# DM3390_Power_Supply.net
KiCad netlist of a schematic drawn in Altium Designer
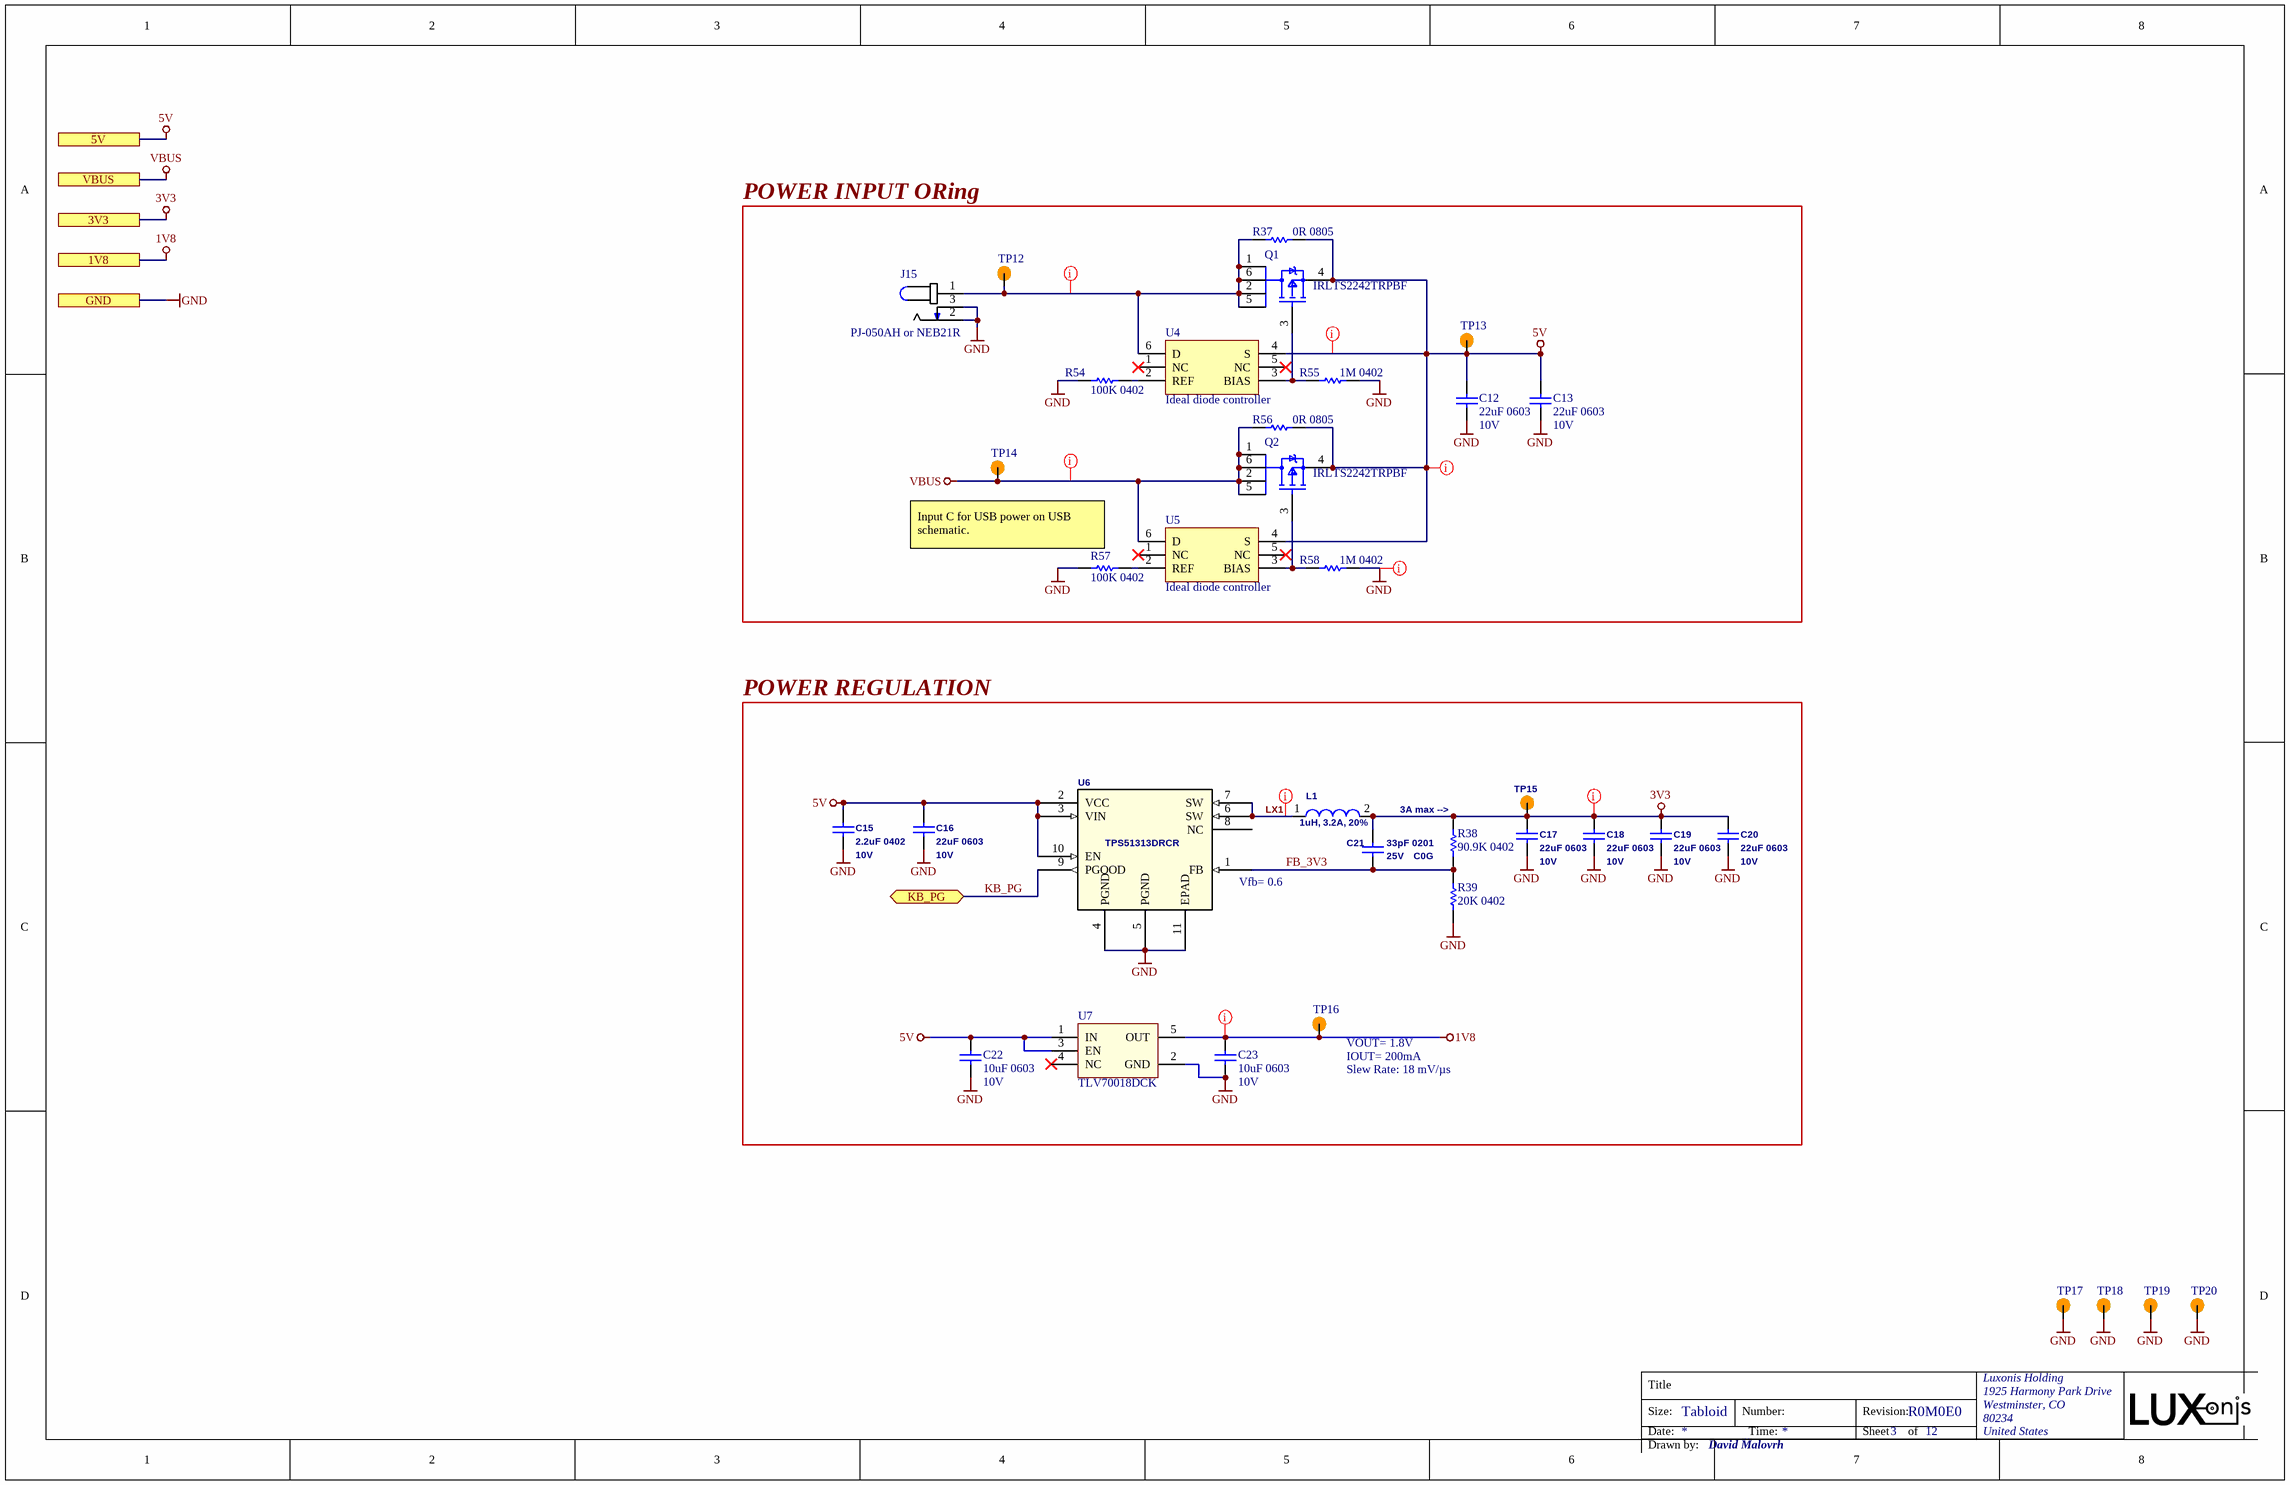
[diagram p0: DM3390_Power_Supply.SchDoc]

(export (version "E")
  (design (tool "Eeschema 10.0.6"))
  (components
    (comp (ref "C12")
      (value "22uF 0603")
      (footprint "CAP_Altium_Vault_Generic:CAPC0603(1608)100_L")
      (description "CAP CER 22UF 10V X5R 0603 20%")
      (fields (field (name "TOLERANCE") "20%") (field (name "VOLTAGE RATING") "10V"))
      (libsource (lib "LuxonisMaster") (part "GRM188R61A226ME15D"))
    )
    (comp (ref "C13")
      (value "22uF 0603")
      (footprint "CAP_Altium_Vault_Generic:CAPC0603(1608)100_L")
      (description "CAP CER 22UF 10V X5R 0603 20%")
      (fields (field (name "TOLERANCE") "20%") (field (name "VOLTAGE RATING") "10V"))
      (libsource (lib "LuxonisMaster") (part "GRM188R61A226ME15D"))
    )
    (comp (ref "C15")
      (value "2.2uF 0402")
      (footprint "CAP_Altium_Vault_Generic:CAPC0402(1005)70_L")
      (description "CAP CER 2.2UF 10V X5R 0402 10%")
      (fields (field (name "TOLERANCE") "10%") (field (name "VOLTAGE RATING") "10V"))
      (libsource (lib "LuxonisMaster") (part "GRM155R61A225KE95D"))
    )
    (comp (ref "C16")
      (value "22uF 0603")
      (footprint "CAP_Altium_Vault_Generic:CAPC0603(1608)100_L")
      (description "CAP CER 22UF 10V X5R 0603 20%")
      (fields (field (name "TOLERANCE") "20%") (field (name "VOLTAGE RATING") "10V"))
      (libsource (lib "LuxonisMaster") (part "GRM188R61A226ME15D"))
    )
    (comp (ref "C17")
      (value "22uF 0603")
      (footprint "CAP_Altium_Vault_Generic:CAPC0603(1608)100_L")
      (description "CAP CER 22UF 10V X5R 0603 20%")
      (fields (field (name "TOLERANCE") "20%") (field (name "VOLTAGE RATING") "10V"))
      (libsource (lib "LuxonisMaster") (part "GRM188R61A226ME15D"))
    )
    (comp (ref "C18")
      (value "22uF 0603")
      (footprint "CAP_Altium_Vault_Generic:CAPC0603(1608)100_L")
      (description "CAP CER 22UF 10V X5R 0603 20%")
      (fields (field (name "TOLERANCE") "20%") (field (name "VOLTAGE RATING") "10V"))
      (libsource (lib "LuxonisMaster") (part "GRM188R61A226ME15D"))
    )
    (comp (ref "C19")
      (value "22uF 0603")
      (footprint "CAP_Altium_Vault_Generic:CAPC0603(1608)100_L")
      (description "CAP CER 22UF 10V X5R 0603 20%")
      (fields (field (name "TOLERANCE") "20%") (field (name "VOLTAGE RATING") "10V"))
      (libsource (lib "LuxonisMaster") (part "GRM188R61A226ME15D"))
    )
    (comp (ref "C20")
      (value "22uF 0603")
      (footprint "CAP_Altium_Vault_Generic:CAPC0603(1608)100_L")
      (description "CAP CER 22UF 10V X5R 0603 20%")
      (fields (field (name "TOLERANCE") "20%") (field (name "VOLTAGE RATING") "10V"))
      (libsource (lib "LuxonisMaster") (part "GRM188R61A226ME15D"))
    )
    (comp (ref "C21")
      (value "33pF 0201")
      (footprint "CAP_Altium_Vault_Generic:CAPC0201(0603)33_L")
      (description "CAP CER 33PF 25V C0G/NP0 0201")
      (fields
        (field (name "TOLERANCE") "5%")
        (field (name "VOLTAGE RATING") "25V")
        (field (name "DIELECTRIC") "C0G")
      )
      (libsource (lib "LuxonisMaster") (part "GRM0335C1E330JA01D"))
    )
    (comp (ref "C22")
      (value "10uF 0603")
      (footprint "CAP_Altium_Vault_Generic:CAPC0603(1608)100_L")
      (description "CAP CER 10UF 10V X5R 0603 20%")
      (fields (field (name "TOLERANCE") "20%") (field (name "VOLTAGE RATING") "10V"))
      (libsource (lib "LuxonisMaster") (part "GRM188R61A106ME69D"))
    )
    (comp (ref "C23")
      (value "10uF 0603")
      (footprint "CAP_Altium_Vault_Generic:CAPC0603(1608)100_L")
      (description "CAP CER 10UF 10V X5R 0603 20%")
      (fields (field (name "TOLERANCE") "20%") (field (name "VOLTAGE RATING") "10V"))
      (libsource (lib "LuxonisMaster") (part "GRM188R61A106ME69D"))
    )
    (comp (ref "J15")
      (value "PJ-050AH or NEB21R")
      (footprint "LuxonisMaster:PJ-050AH/NEB21R_COMBO")
      (description "CONN POWER PIN 2 POS RA PTH Barrel jack 2.1mm x 5.5mm combo footprint")
      (libsource (lib "LuxonisMaster") (part "PJ-050AH/NEB21R_COMBO"))
    )
    (comp (ref "L1")
      (value "1uH, 3.2A, 20%")
      (footprint "LuxonisMaster:DFE252012P-1R0M=P2")
      (description "FIXED IND 1UH 3.2A 42 MOHM SMD")
      (fields
        (field (name "MANUFACTURER") "Murata")
        (field (name "MANUFACTURER PART NUMBER") "DFE252012P-1R0M=P2")
      )
      (libsource (lib "LuxonisMaster") (part "DFE252012P-1R0M=P2"))
    )
    (comp (ref "Q1")
      (value "IRLTS2242TRPBF")
      (footprint "TSOP-6-MFG")
      (description "MOSFET P-CH 20V 6.9A 6TSOP")
      (libsource (lib "LuxonisMaster") (part "IRLTS2242TRPBF"))
    )
    (comp (ref "Q2")
      (value "IRLTS2242TRPBF")
      (footprint "TSOP-6-MFG")
      (description "MOSFET P-CH 20V 6.9A 6TSOP")
      (libsource (lib "LuxonisMaster") (part "IRLTS2242TRPBF"))
    )
    (comp (ref "R37")
      (value "0R 0805")
      (footprint "RESC0805(2012)_L")
      (description "RES SMD 0.0R OHM 1% 1/8W 0805")
      (libsource (lib "LuxonisMaster") (part "CRCW08050000Z0EA"))
    )
    (comp (ref "R38")
      (value "90.9K 0402")
      (footprint "RES_Altium_Vault_Generic:RESC0402(1005)_L")
      (description "RES SMD 90.9K OHM 1% 1/16W 0402")
      (fields (field (name "TOLERANCE") "1%"))
      (libsource (lib "LuxonisMaster") (part "CRCW040290K9FKED"))
    )
    (comp (ref "R39")
      (value "20K 0402")
      (footprint "RES_Altium_Vault_Generic:RESC0402(1005)_L")
      (fields
        (field (name "MANUFACTURER") "Yageo")
        (field (name "MANUFACTURER PART NUMBER") "RC0402FR-0720KL")
        (field (name "TOLERANCE") "1%")
      )
      (libsource (lib "LuxonisMaster") (part "RC0402FR-0720KL"))
    )
    (comp (ref "R54")
      (value "100K 0402")
      (footprint "RES_Altium_Vault_Generic:RESC0402(1005)_L")
      (description "RES SMD 100K OHM 1% 1/16W 0402")
      (fields (field (name "TOLERANCE") "1%"))
      (libsource (lib "LuxonisMaster") (part "RC0402FR-07100KL"))
    )
    (comp (ref "R55")
      (value "1M 0402")
      (footprint "RES_Altium_Vault_Generic:RESC0402(1005)_L")
      (description "RES SMD 1M OHM 1% 1/16W 0402")
      (fields (field (name "TOLERANCE") "1%"))
      (libsource (lib "LuxonisMaster") (part "RC0402FR-071ML"))
    )
    (comp (ref "R56")
      (value "0R 0805")
      (footprint "RESC0805(2012)_L")
      (description "RES SMD 0.0R OHM 1% 1/8W 0805")
      (libsource (lib "LuxonisMaster") (part "CRCW08050000Z0EA"))
    )
    (comp (ref "R57")
      (value "100K 0402")
      (footprint "RES_Altium_Vault_Generic:RESC0402(1005)_L")
      (description "RES SMD 100K OHM 1% 1/16W 0402")
      (fields (field (name "TOLERANCE") "1%"))
      (libsource (lib "LuxonisMaster") (part "RC0402FR-07100KL"))
    )
    (comp (ref "R58")
      (value "1M 0402")
      (footprint "RES_Altium_Vault_Generic:RESC0402(1005)_L")
      (description "RES SMD 1M OHM 1% 1/16W 0402")
      (fields (field (name "TOLERANCE") "1%"))
      (libsource (lib "LuxonisMaster") (part "RC0402FR-071ML"))
    )
    (comp (ref "TP12")
      (value "TP100_200_NS")
      (footprint "LuxonisMaster:TP100_200_NS")
      (libsource (lib "LuxonisMaster") (part "TEST_POINT"))
    )
    (comp (ref "TP13")
      (value "TP100_200_NS")
      (footprint "LuxonisMaster:TP100_200_NS")
      (libsource (lib "LuxonisMaster") (part "TEST_POINT"))
    )
    (comp (ref "TP14")
      (value "TP100_200_NS")
      (footprint "LuxonisMaster:TP100_200_NS")
      (libsource (lib "LuxonisMaster") (part "TEST_POINT"))
    )
    (comp (ref "TP15")
      (value "TP075_150_NS")
      (footprint "LuxonisMaster:TP075_150_NS")
      (libsource (lib "LuxonisMaster") (part "TEST_POINT"))
    )
    (comp (ref "TP16")
      (value "TP100_200_NS")
      (footprint "LuxonisMaster:TP100_200_NS")
      (libsource (lib "LuxonisMaster") (part "TEST_POINT"))
    )
    (comp (ref "TP17")
      (value "TP100_200_NS")
      (footprint "LuxonisMaster:TP100_200_NS")
      (libsource (lib "LuxonisMaster") (part "TEST_POINT"))
    )
    (comp (ref "TP18")
      (value "TP100_200_NS")
      (footprint "LuxonisMaster:TP100_200_NS")
      (libsource (lib "LuxonisMaster") (part "TEST_POINT"))
    )
    (comp (ref "TP19")
      (value "TP100_200_NS")
      (footprint "LuxonisMaster:TP100_200_NS")
      (libsource (lib "LuxonisMaster") (part "TEST_POINT"))
    )
    (comp (ref "TP20")
      (value "TP100_200_NS")
      (footprint "LuxonisMaster:TP100_200_NS")
      (libsource (lib "LuxonisMaster") (part "TEST_POINT"))
    )
    (comp (ref "U4")
      (value "Ideal diode controller")
      (footprint "DZDH0401DW")
      (description "Ideal Diode Controller 40V 300mA 300mW 6-Pin SOT-363 T/R")
      (libsource (lib "LuxonisMaster") (part "DZDH0401DW"))
    )
    (comp (ref "U5")
      (value "Ideal diode controller")
      (footprint "DZDH0401DW")
      (description "Ideal Diode Controller 40V 300mA 300mW 6-Pin SOT-363 T/R")
      (libsource (lib "LuxonisMaster") (part "DZDH0401DW"))
    )
    (comp (ref "U6")
      (value "TPS51313DRCR")
      (footprint "VSON-TPS51313DRCR")
      (description "Switching Regulator, Voltage-mode, 3A, 1000kHz Switching Freq-Max, PDSO10")
      (libsource (lib "LuxonisMaster") (part "TPS51313DRCR"))
    )
    (comp (ref "U7")
      (value "TLV70018DCK")
      (footprint "LuxonisMaster:TLV70018DCK")
      (description "IC REG LINEAR 1.8V 200MA SC70-5 Linear Voltage Regulator IC  1 Output  200mA SC-70-5")
      (libsource (lib "LuxonisMaster") (part "TLV70018DCK"))
    )
  )
  (nets
    (net (code "1") (name "/FB_3V3") (class "Default")
      (node (ref "C21") (pin "1") (pinfunction "1_1") (pintype "passive"))
      (node (ref "R38") (pin "1") (pinfunction "1_1") (pintype "passive"))
      (node (ref "R39") (pin "2") (pinfunction "2_2") (pintype "passive"))
      (node (ref "U6") (pin "1") (pinfunction "FB_1") (pintype "input"))
    )
    (net (code "2") (name "/KB_PG") (class "Default")
      (node (ref "U6") (pin "9") (pinfunction "PGOOD_9") (pintype "output"))
    )
    (net (code "3") (name "/LX1") (class "Default")
      (node (ref "L1") (pin "1") (pinfunction "1_1") (pintype "passive"))
      (node (ref "U6") (pin "6") (pinfunction "SW_6") (pintype "input"))
      (node (ref "U6") (pin "7") (pinfunction "SW_7") (pintype "input"))
    )
    (net (code "4") (name "1V8") (class "Default")
      (node (ref "C23") (pin "2") (pinfunction "2_2") (pintype "passive"))
      (node (ref "TP16") (pin "1") (pintype "passive"))
      (node (ref "U7") (pin "5") (pinfunction "OUT_5") (pintype "passive"))
    )
    (net (code "5") (name "3V3") (class "Default")
      (node (ref "C17") (pin "1") (pinfunction "1_1") (pintype "passive"))
      (node (ref "C18") (pin "1") (pinfunction "1_1") (pintype "passive"))
      (node (ref "C19") (pin "1") (pinfunction "1_1") (pintype "passive"))
      (node (ref "C20") (pin "1") (pinfunction "1_1") (pintype "passive"))
      (node (ref "C21") (pin "2") (pinfunction "2_2") (pintype "passive"))
      (node (ref "L1") (pin "2") (pinfunction "2_2") (pintype "passive"))
      (node (ref "R38") (pin "2") (pinfunction "2_2") (pintype "passive"))
      (node (ref "TP15") (pin "1") (pintype "passive"))
    )
    (net (code "6") (name "5V") (class "Default")
      (node (ref "C12") (pin "2") (pinfunction "2_2") (pintype "passive"))
      (node (ref "C13") (pin "2") (pinfunction "2_2") (pintype "passive"))
      (node (ref "C15") (pin "1") (pinfunction "1_1") (pintype "passive"))
      (node (ref "C16") (pin "1") (pinfunction "1_1") (pintype "passive"))
      (node (ref "C22") (pin "2") (pinfunction "2_2") (pintype "passive"))
      (node (ref "Q1") (pin "4") (pinfunction "S_4") (pintype "passive"))
      (node (ref "Q2") (pin "4") (pinfunction "S_4") (pintype "passive"))
      (node (ref "R37") (pin "2") (pinfunction "2_2") (pintype "passive"))
      (node (ref "R56") (pin "2") (pinfunction "2_2") (pintype "passive"))
      (node (ref "TP13") (pin "1") (pintype "passive"))
      (node (ref "U4") (pin "4") (pinfunction "S_4") (pintype "passive"))
      (node (ref "U5") (pin "4") (pinfunction "S_4") (pintype "passive"))
      (node (ref "U6") (pin "10") (pinfunction "EN_10") (pintype "input"))
      (node (ref "U6") (pin "2") (pinfunction "VCC_2") (pintype "power_in"))
      (node (ref "U6") (pin "3") (pinfunction "VIN_3") (pintype "input"))
      (node (ref "U7") (pin "1") (pinfunction "IN_1") (pintype "passive"))
      (node (ref "U7") (pin "3") (pinfunction "EN_3") (pintype "passive"))
    )
    (net (code "7") (name "GND") (class "Default")
      (node (ref "C12") (pin "1") (pinfunction "1_1") (pintype "passive"))
      (node (ref "C13") (pin "1") (pinfunction "1_1") (pintype "passive"))
      (node (ref "C15") (pin "2") (pinfunction "2_2") (pintype "passive"))
      (node (ref "C16") (pin "2") (pinfunction "2_2") (pintype "passive"))
      (node (ref "C17") (pin "2") (pinfunction "2_2") (pintype "passive"))
      (node (ref "C18") (pin "2") (pinfunction "2_2") (pintype "passive"))
      (node (ref "C19") (pin "2") (pinfunction "2_2") (pintype "passive"))
      (node (ref "C20") (pin "2") (pinfunction "2_2") (pintype "passive"))
      (node (ref "C22") (pin "1") (pinfunction "1_1") (pintype "passive"))
      (node (ref "C23") (pin "1") (pinfunction "1_1") (pintype "passive"))
      (node (ref "J15") (pin "2") (pinfunction "2_2") (pintype "passive"))
      (node (ref "J15") (pin "3") (pinfunction "3_3") (pintype "passive"))
      (node (ref "R39") (pin "1") (pinfunction "1_1") (pintype "passive"))
      (node (ref "R54") (pin "1") (pinfunction "1_1") (pintype "passive"))
      (node (ref "R55") (pin "1") (pinfunction "1_1") (pintype "passive"))
      (node (ref "R57") (pin "1") (pinfunction "1_1") (pintype "passive"))
      (node (ref "R58") (pin "1") (pinfunction "1_1") (pintype "passive"))
      (node (ref "TP17") (pin "1") (pintype "passive"))
      (node (ref "TP18") (pin "1") (pintype "passive"))
      (node (ref "TP19") (pin "1") (pintype "passive"))
      (node (ref "TP20") (pin "1") (pintype "passive"))
      (node (ref "U6") (pin "11") (pinfunction "EPAD_11") (pintype "passive"))
      (node (ref "U6") (pin "4") (pinfunction "PGND_4") (pintype "power_in"))
      (node (ref "U6") (pin "5") (pinfunction "PGND_5") (pintype "power_in"))
      (node (ref "U7") (pin "2") (pinfunction "GND_2") (pintype "passive"))
    )
    (net (code "8") (name "Net-(Q1-G)") (class "Default")
      (node (ref "Q1") (pin "3") (pinfunction "G_3") (pintype "passive"))
      (node (ref "R55") (pin "2") (pinfunction "2_2") (pintype "passive"))
      (node (ref "U4") (pin "3") (pinfunction "BIAS_3") (pintype "passive"))
    )
    (net (code "9") (name "Net-(Q2-G)") (class "Default")
      (node (ref "Q2") (pin "3") (pinfunction "G_3") (pintype "passive"))
      (node (ref "R58") (pin "2") (pinfunction "2_2") (pintype "passive"))
      (node (ref "U5") (pin "3") (pinfunction "BIAS_3") (pintype "passive"))
    )
    (net (code "10") (name "Net-(U4-D)") (class "Default")
      (node (ref "J15") (pin "1") (pinfunction "1_1") (pintype "passive"))
      (node (ref "Q1") (pin "1") (pinfunction "D_1") (pintype "passive"))
      (node (ref "Q1") (pin "2") (pinfunction "D_2") (pintype "passive"))
      (node (ref "Q1") (pin "5") (pinfunction "D_5") (pintype "passive"))
      (node (ref "Q1") (pin "6") (pinfunction "D_6") (pintype "passive"))
      (node (ref "R37") (pin "1") (pinfunction "1_1") (pintype "passive"))
      (node (ref "TP12") (pin "1") (pintype "passive"))
      (node (ref "U4") (pin "6") (pinfunction "D_6") (pintype "passive"))
    )
    (net (code "11") (name "Net-(U4-REF)") (class "Default")
      (node (ref "R54") (pin "2") (pinfunction "2_2") (pintype "passive"))
      (node (ref "U4") (pin "2") (pinfunction "REF_2") (pintype "passive"))
    )
    (net (code "12") (name "Net-(U5-REF)") (class "Default")
      (node (ref "R57") (pin "2") (pinfunction "2_2") (pintype "passive"))
      (node (ref "U5") (pin "2") (pinfunction "REF_2") (pintype "passive"))
    )
    (net (code "13") (name "VBUS") (class "Default")
      (node (ref "Q2") (pin "1") (pinfunction "D_1") (pintype "passive"))
      (node (ref "Q2") (pin "2") (pinfunction "D_2") (pintype "passive"))
      (node (ref "Q2") (pin "5") (pinfunction "D_5") (pintype "passive"))
      (node (ref "Q2") (pin "6") (pinfunction "D_6") (pintype "passive"))
      (node (ref "R56") (pin "1") (pinfunction "1_1") (pintype "passive"))
      (node (ref "TP14") (pin "1") (pintype "passive"))
      (node (ref "U5") (pin "6") (pinfunction "D_6") (pintype "passive"))
    )
    (net (code "14") (name "unconnected-(U4-NC-Pad1)") (class "Default")
      (node (ref "U4") (pin "1") (pinfunction "NC_1") (pintype "passive+no_connect"))
    )
    (net (code "15") (name "unconnected-(U4-NC-Pad5)") (class "Default")
      (node (ref "U4") (pin "5") (pinfunction "NC_5") (pintype "passive+no_connect"))
    )
    (net (code "16") (name "unconnected-(U5-NC-Pad1)") (class "Default")
      (node (ref "U5") (pin "1") (pinfunction "NC_1") (pintype "passive+no_connect"))
    )
    (net (code "17") (name "unconnected-(U5-NC-Pad5)") (class "Default")
      (node (ref "U5") (pin "5") (pinfunction "NC_5") (pintype "passive+no_connect"))
    )
    (net (code "18") (name "unconnected-(U6-NC-Pad8)") (class "Default")
      (node (ref "U6") (pin "8") (pinfunction "NC_8") (pintype "passive"))
    )
    (net (code "19") (name "unconnected-(U7-NC-Pad4)") (class "Default")
      (node (ref "U7") (pin "4") (pinfunction "NC_4") (pintype "passive+no_connect"))
    )
  )
)
